# Output.net
KiCad netlist of a schematic drawn in Altium Designer
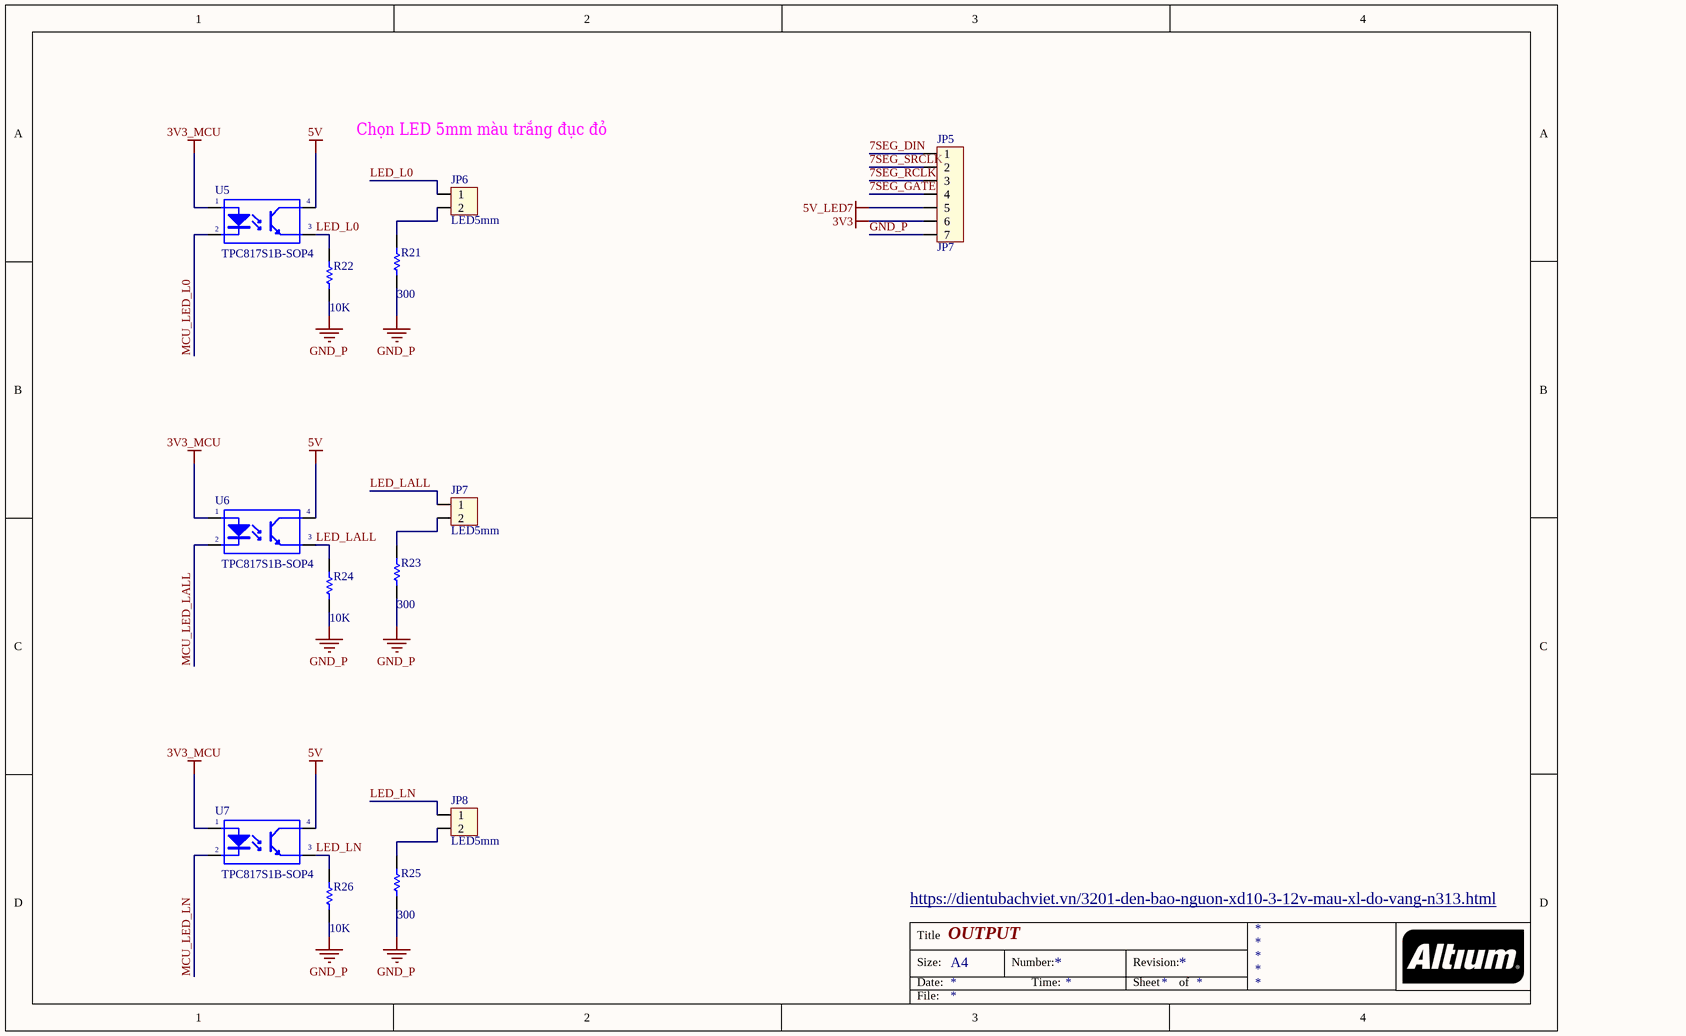
[diagram p0: Output.SchDoc]

(export (version "E")
  (design (tool "Eeschema 10.0.6"))
  (components
    (comp (ref "JP5")
      (value "JP7")
      (footprint "CON7")
      (description "Connector 7")
      (libsource (lib "lpson") (part "Con7"))
    )
    (comp (ref "JP6")
      (value "LED5mm")
      (footprint "CON2")
      (description "Connector 2")
      (libsource (lib "lpson") (part "Con2"))
    )
    (comp (ref "JP7")
      (value "LED5mm")
      (footprint "CON2")
      (description "Connector 2")
      (libsource (lib "lpson") (part "Con2"))
    )
    (comp (ref "JP8")
      (value "LED5mm")
      (footprint "CON2")
      (description "Connector 2")
      (libsource (lib "lpson") (part "Con2"))
    )
    (comp (ref "R21")
      (value "300")
      (footprint "Res 0805 SMD")
      (description "RES SMD 249K OHM 1% 1/10W 0805")
      (fields
        (field (name "MANUFACTURER") "Yageo")
        (field (name "MANUFACTURER PART NUMBER") "RC0603FR-07249KL")
      )
      (libsource (lib "GSHT_181013") (part "249K/R0805/1%"))
    )
    (comp (ref "R22")
      (value "10K")
      (footprint "Res 0805 SMD")
      (description "RES SMD 249K OHM 1% 1/10W 0805")
      (fields
        (field (name "MANUFACTURER") "Yageo")
        (field (name "MANUFACTURER PART NUMBER") "RC0603FR-07249KL")
      )
      (libsource (lib "GSHT_181013") (part "249K/R0805/1%"))
    )
    (comp (ref "R23")
      (value "300")
      (footprint "Res 0805 SMD")
      (description "RES SMD 249K OHM 1% 1/10W 0805")
      (fields
        (field (name "MANUFACTURER") "Yageo")
        (field (name "MANUFACTURER PART NUMBER") "RC0603FR-07249KL")
      )
      (libsource (lib "GSHT_181013") (part "249K/R0805/1%"))
    )
    (comp (ref "R24")
      (value "10K")
      (footprint "Res 0805 SMD")
      (description "RES SMD 249K OHM 1% 1/10W 0805")
      (fields
        (field (name "MANUFACTURER") "Yageo")
        (field (name "MANUFACTURER PART NUMBER") "RC0603FR-07249KL")
      )
      (libsource (lib "GSHT_181013") (part "249K/R0805/1%"))
    )
    (comp (ref "R25")
      (value "300")
      (footprint "Res 0805 SMD")
      (description "RES SMD 249K OHM 1% 1/10W 0805")
      (fields
        (field (name "MANUFACTURER") "Yageo")
        (field (name "MANUFACTURER PART NUMBER") "RC0603FR-07249KL")
      )
      (libsource (lib "GSHT_181013") (part "249K/R0805/1%"))
    )
    (comp (ref "R26")
      (value "10K")
      (footprint "Res 0805 SMD")
      (description "RES SMD 249K OHM 1% 1/10W 0805")
      (fields
        (field (name "MANUFACTURER") "Yageo")
        (field (name "MANUFACTURER PART NUMBER") "RC0603FR-07249KL")
      )
      (libsource (lib "GSHT_181013") (part "249K/R0805/1%"))
    )
    (comp (ref "U5")
      (value "TPC817S1B-SOP4")
      (footprint "TPC817-4SOP")
      (description "Optoisolator Transistor Output 5000Vrms 1 Channel 4-SOP")
      (libsource (lib "lpson") (part "PC817"))
    )
    (comp (ref "U6")
      (value "TPC817S1B-SOP4")
      (footprint "TPC817-4SOP")
      (description "Optoisolator Transistor Output 5000Vrms 1 Channel 4-SOP")
      (libsource (lib "lpson") (part "PC817"))
    )
    (comp (ref "U7")
      (value "TPC817S1B-SOP4")
      (footprint "TPC817-4SOP")
      (description "Optoisolator Transistor Output 5000Vrms 1 Channel 4-SOP")
      (libsource (lib "lpson") (part "PC817"))
    )
  )
  (nets
    (net (code "1") (name "/7SEG_DIN") (class "Default")
      (node (ref "JP5") (pin "1") (pinfunction "1_1") (pintype "passive"))
    )
    (net (code "2") (name "/7SEG_GATE") (class "Default")
      (node (ref "JP5") (pin "4") (pinfunction "4_4") (pintype "passive"))
    )
    (net (code "3") (name "/7SEG_RCLK") (class "Default")
      (node (ref "JP5") (pin "3") (pinfunction "3_3") (pintype "passive"))
    )
    (net (code "4") (name "/7SEG_SRCLK") (class "Default")
      (node (ref "JP5") (pin "2") (pinfunction "2_2") (pintype "passive"))
    )
    (net (code "5") (name "/LED_L0") (class "Default")
      (node (ref "JP6") (pin "1") (pinfunction "1_1") (pintype "passive"))
      (node (ref "R22") (pin "2") (pinfunction "2_2") (pintype "passive"))
      (node (ref "U5") (pin "3") (pinfunction "E_3") (pintype "passive"))
    )
    (net (code "6") (name "/LED_LALL") (class "Default")
      (node (ref "JP7") (pin "1") (pinfunction "1_1") (pintype "passive"))
      (node (ref "R24") (pin "2") (pinfunction "2_2") (pintype "passive"))
      (node (ref "U6") (pin "3") (pinfunction "E_3") (pintype "passive"))
    )
    (net (code "7") (name "/LED_LN") (class "Default")
      (node (ref "JP8") (pin "1") (pinfunction "1_1") (pintype "passive"))
      (node (ref "R26") (pin "2") (pinfunction "2_2") (pintype "passive"))
      (node (ref "U7") (pin "3") (pinfunction "E_3") (pintype "passive"))
    )
    (net (code "8") (name "/MCU_LED_L0") (class "Default")
      (node (ref "U5") (pin "2") (pinfunction "K_2") (pintype "passive"))
    )
    (net (code "9") (name "/MCU_LED_LALL") (class "Default")
      (node (ref "U6") (pin "2") (pinfunction "K_2") (pintype "passive"))
    )
    (net (code "10") (name "/MCU_LED_LN") (class "Default")
      (node (ref "U7") (pin "2") (pinfunction "K_2") (pintype "passive"))
    )
    (net (code "11") (name "3V3") (class "Default")
      (node (ref "JP5") (pin "6") (pinfunction "6_6") (pintype "passive"))
    )
    (net (code "12") (name "3V3_MCU") (class "Default")
      (node (ref "U5") (pin "1") (pinfunction "A_1") (pintype "passive"))
      (node (ref "U6") (pin "1") (pinfunction "A_1") (pintype "passive"))
      (node (ref "U7") (pin "1") (pinfunction "A_1") (pintype "passive"))
    )
    (net (code "13") (name "5V") (class "Default")
      (node (ref "U5") (pin "4") (pinfunction "C_4") (pintype "passive"))
      (node (ref "U6") (pin "4") (pinfunction "C_4") (pintype "passive"))
      (node (ref "U7") (pin "4") (pinfunction "C_4") (pintype "passive"))
    )
    (net (code "14") (name "5V_LED7") (class "Default")
      (node (ref "JP5") (pin "5") (pinfunction "5_5") (pintype "passive"))
    )
    (net (code "15") (name "GND_P") (class "Default")
      (node (ref "JP5") (pin "7") (pinfunction "7_7") (pintype "passive"))
      (node (ref "R21") (pin "1") (pinfunction "1_1") (pintype "passive"))
      (node (ref "R22") (pin "1") (pinfunction "1_1") (pintype "passive"))
      (node (ref "R23") (pin "1") (pinfunction "1_1") (pintype "passive"))
      (node (ref "R24") (pin "1") (pinfunction "1_1") (pintype "passive"))
      (node (ref "R25") (pin "1") (pinfunction "1_1") (pintype "passive"))
      (node (ref "R26") (pin "1") (pinfunction "1_1") (pintype "passive"))
    )
    (net (code "16") (name "Net-(JP6-Pad2)") (class "Default")
      (node (ref "JP6") (pin "2") (pinfunction "2_2") (pintype "passive"))
      (node (ref "R21") (pin "2") (pinfunction "2_2") (pintype "passive"))
    )
    (net (code "17") (name "Net-(JP7-Pad2)") (class "Default")
      (node (ref "JP7") (pin "2") (pinfunction "2_2") (pintype "passive"))
      (node (ref "R23") (pin "2") (pinfunction "2_2") (pintype "passive"))
    )
    (net (code "18") (name "Net-(JP8-Pad2)") (class "Default")
      (node (ref "JP8") (pin "2") (pinfunction "2_2") (pintype "passive"))
      (node (ref "R25") (pin "2") (pinfunction "2_2") (pintype "passive"))
    )
  )
)
